# DemodTeensy.net
KiCad netlist of a schematic drawn in Altium Designer
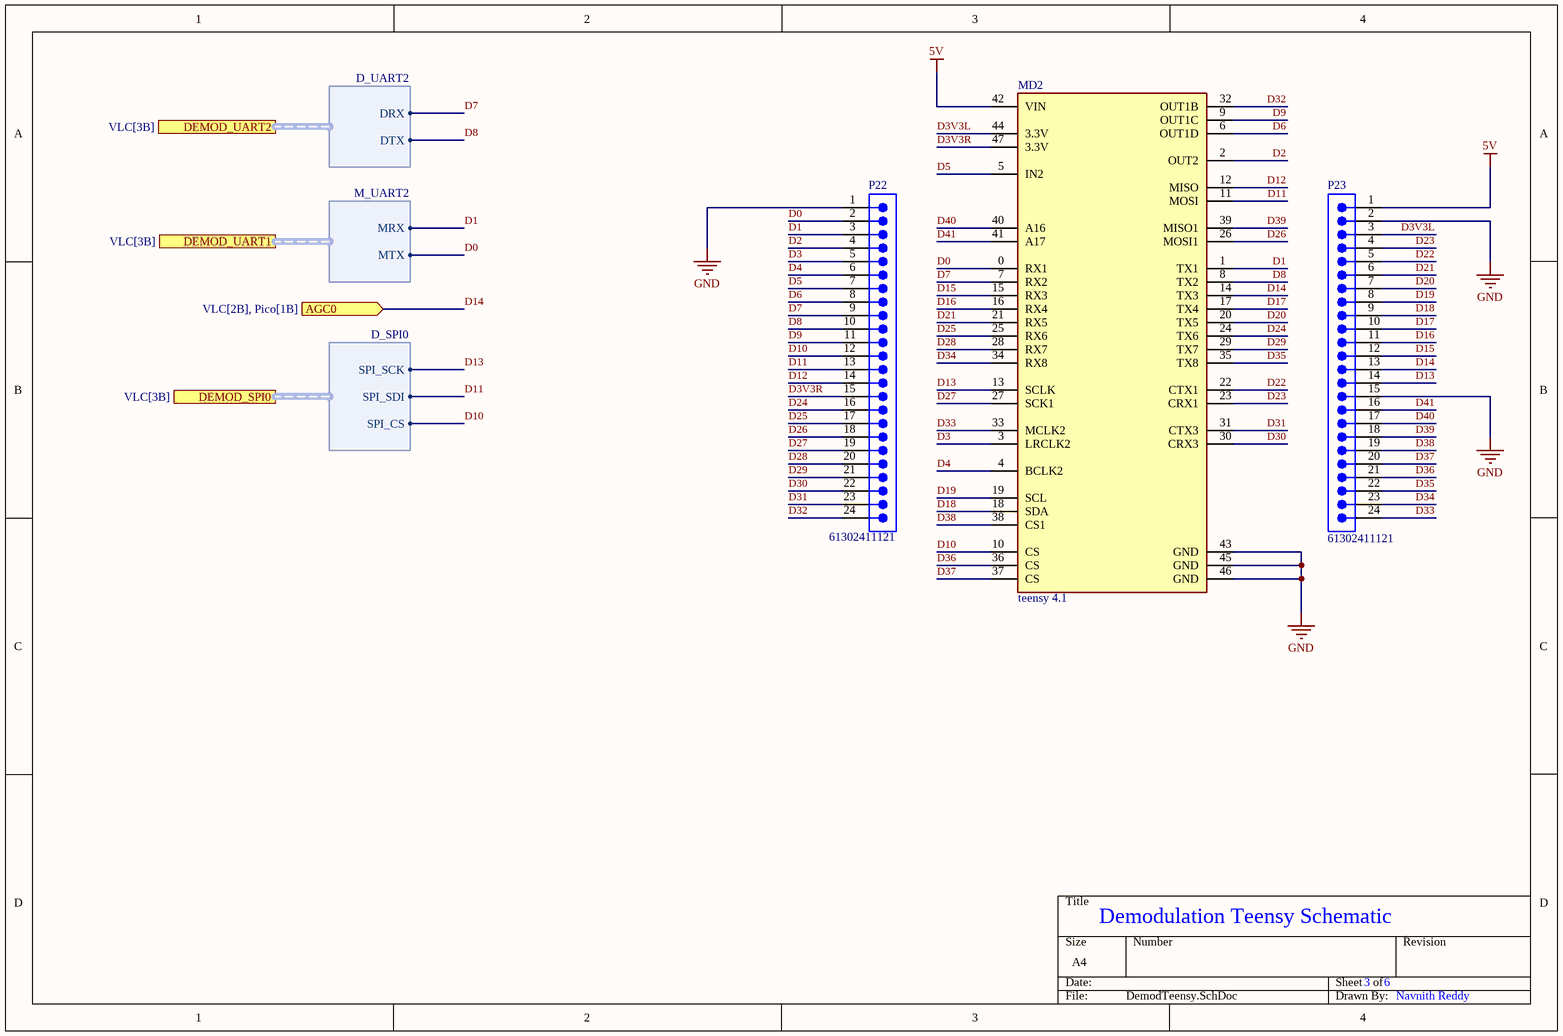
[diagram p0: DemodTeensy.SchDoc]

(export (version "E")
  (design (tool "Eeschema 10.0.6"))
  (components
    (comp (ref "MD2")
      (value "teensy 4.1")
      (footprint "FP-DEV-16996-MFG")
      (description "TEENSY 4.1 (HEADERS)")
      (libsource (lib "Altium Content Vault") (part "080115a1ce54750370cf87ec145ee29"))
    )
    (comp (ref "P22")
      (value "61302411121")
      (footprint "61302411121")
      (libsource (lib "Altium Content Vault") (part "Header_Male_1R_24P"))
    )
    (comp (ref "P23")
      (value "61302411121")
      (footprint "61302411121")
      (libsource (lib "Altium Content Vault") (part "Header_Male_1R_24P"))
    )
  )
  (nets
    (net (code "4") (name "/D0") (class "Default")
      (node (ref "MD2") (pin "0") (pinfunction "RX1_0") (pintype "passive"))
      (node (ref "P22") (pin "2") (pinfunction "2_2") (pintype "passive"))
    )
    (net (code "5") (name "/D1") (class "Default")
      (node (ref "MD2") (pin "1") (pinfunction "TX1_1") (pintype "passive"))
      (node (ref "P22") (pin "3") (pinfunction "3_3") (pintype "passive"))
    )
    (net (code "6") (name "/D2") (class "Default")
      (node (ref "MD2") (pin "2") (pinfunction "OUT2_2") (pintype "passive"))
      (node (ref "P22") (pin "4") (pinfunction "4_4") (pintype "passive"))
    )
    (net (code "7") (name "/D3") (class "Default")
      (node (ref "MD2") (pin "3") (pinfunction "LRCLK2_3") (pintype "passive"))
      (node (ref "P22") (pin "5") (pinfunction "5_5") (pintype "passive"))
    )
    (net (code "8") (name "/D3V3L") (class "Default")
      (node (ref "MD2") (pin "44") (pinfunction "3.3V_44") (pintype "passive"))
      (node (ref "P23") (pin "3") (pinfunction "3_3") (pintype "passive"))
    )
    (net (code "9") (name "/D3V3R") (class "Default")
      (node (ref "MD2") (pin "47") (pinfunction "3.3V_47") (pintype "passive"))
      (node (ref "P22") (pin "15") (pinfunction "15_15") (pintype "passive"))
    )
    (net (code "10") (name "/D4") (class "Default")
      (node (ref "MD2") (pin "4") (pinfunction "BCLK2_4") (pintype "passive"))
      (node (ref "P22") (pin "6") (pinfunction "6_6") (pintype "passive"))
    )
    (net (code "11") (name "/D5") (class "Default")
      (node (ref "MD2") (pin "5") (pinfunction "IN2_5") (pintype "passive"))
      (node (ref "P22") (pin "7") (pinfunction "7_7") (pintype "passive"))
    )
    (net (code "12") (name "/D6") (class "Default")
      (node (ref "MD2") (pin "6") (pinfunction "OUT1D_6") (pintype "passive"))
      (node (ref "P22") (pin "8") (pinfunction "8_8") (pintype "passive"))
    )
    (net (code "13") (name "/D7") (class "Default")
      (node (ref "MD2") (pin "7") (pinfunction "RX2_7") (pintype "passive"))
      (node (ref "P22") (pin "9") (pinfunction "9_9") (pintype "passive"))
    )
    (net (code "14") (name "/D8") (class "Default")
      (node (ref "MD2") (pin "8") (pinfunction "TX2_8") (pintype "passive"))
      (node (ref "P22") (pin "10") (pinfunction "10_10") (pintype "passive"))
    )
    (net (code "15") (name "/D9") (class "Default")
      (node (ref "MD2") (pin "9") (pinfunction "OUT1C_9") (pintype "passive"))
      (node (ref "P22") (pin "11") (pinfunction "11_11") (pintype "passive"))
    )
    (net (code "16") (name "/D10") (class "Default")
      (node (ref "MD2") (pin "10") (pinfunction "CS_10") (pintype "passive"))
      (node (ref "P22") (pin "12") (pinfunction "12_12") (pintype "passive"))
    )
    (net (code "17") (name "/D11") (class "Default")
      (node (ref "MD2") (pin "11") (pinfunction "MOSI_11") (pintype "passive"))
      (node (ref "P22") (pin "13") (pinfunction "13_13") (pintype "passive"))
    )
    (net (code "18") (name "/D12") (class "Default")
      (node (ref "MD2") (pin "12") (pinfunction "MISO_12") (pintype "passive"))
      (node (ref "P22") (pin "14") (pinfunction "14_14") (pintype "passive"))
    )
    (net (code "19") (name "/D13") (class "Default")
      (node (ref "MD2") (pin "13") (pinfunction "SCLK_13") (pintype "passive"))
      (node (ref "P23") (pin "14") (pinfunction "14_14") (pintype "passive"))
    )
    (net (code "20") (name "/D14") (class "Default")
      (node (ref "MD2") (pin "14") (pinfunction "TX3_14") (pintype "passive"))
      (node (ref "P23") (pin "13") (pinfunction "13_13") (pintype "passive"))
    )
    (net (code "21") (name "/D15") (class "Default")
      (node (ref "MD2") (pin "15") (pinfunction "RX3_15") (pintype "passive"))
      (node (ref "P23") (pin "12") (pinfunction "12_12") (pintype "passive"))
    )
    (net (code "22") (name "/D16") (class "Default")
      (node (ref "MD2") (pin "16") (pinfunction "RX4_16") (pintype "passive"))
      (node (ref "P23") (pin "11") (pinfunction "11_11") (pintype "passive"))
    )
    (net (code "23") (name "/D17") (class "Default")
      (node (ref "MD2") (pin "17") (pinfunction "TX4_17") (pintype "passive"))
      (node (ref "P23") (pin "10") (pinfunction "10_10") (pintype "passive"))
    )
    (net (code "24") (name "/D18") (class "Default")
      (node (ref "MD2") (pin "18") (pinfunction "SDA_18") (pintype "passive"))
      (node (ref "P23") (pin "9") (pinfunction "9_9") (pintype "passive"))
    )
    (net (code "25") (name "/D19") (class "Default")
      (node (ref "MD2") (pin "19") (pinfunction "SCL_19") (pintype "passive"))
      (node (ref "P23") (pin "8") (pinfunction "8_8") (pintype "passive"))
    )
    (net (code "26") (name "/D20") (class "Default")
      (node (ref "MD2") (pin "20") (pinfunction "TX5_20") (pintype "passive"))
      (node (ref "P23") (pin "7") (pinfunction "7_7") (pintype "passive"))
    )
    (net (code "27") (name "/D21") (class "Default")
      (node (ref "MD2") (pin "21") (pinfunction "RX5_21") (pintype "passive"))
      (node (ref "P23") (pin "6") (pinfunction "6_6") (pintype "passive"))
    )
    (net (code "28") (name "/D22") (class "Default")
      (node (ref "MD2") (pin "22") (pinfunction "CTX1_22") (pintype "passive"))
      (node (ref "P23") (pin "5") (pinfunction "5_5") (pintype "passive"))
    )
    (net (code "29") (name "/D23") (class "Default")
      (node (ref "MD2") (pin "23") (pinfunction "CRX1_23") (pintype "passive"))
      (node (ref "P23") (pin "4") (pinfunction "4_4") (pintype "passive"))
    )
    (net (code "30") (name "/D24") (class "Default")
      (node (ref "MD2") (pin "24") (pinfunction "TX6_24") (pintype "passive"))
      (node (ref "P22") (pin "16") (pinfunction "16_16") (pintype "passive"))
    )
    (net (code "31") (name "/D25") (class "Default")
      (node (ref "MD2") (pin "25") (pinfunction "RX6_25") (pintype "passive"))
      (node (ref "P22") (pin "17") (pinfunction "17_17") (pintype "passive"))
    )
    (net (code "32") (name "/D26") (class "Default")
      (node (ref "MD2") (pin "26") (pinfunction "MOSI1_26") (pintype "passive"))
      (node (ref "P22") (pin "18") (pinfunction "18_18") (pintype "passive"))
    )
    (net (code "33") (name "/D27") (class "Default")
      (node (ref "MD2") (pin "27") (pinfunction "SCK1_27") (pintype "passive"))
      (node (ref "P22") (pin "19") (pinfunction "19_19") (pintype "passive"))
    )
    (net (code "34") (name "/D28") (class "Default")
      (node (ref "MD2") (pin "28") (pinfunction "RX7_28") (pintype "passive"))
      (node (ref "P22") (pin "20") (pinfunction "20_20") (pintype "passive"))
    )
    (net (code "35") (name "/D29") (class "Default")
      (node (ref "MD2") (pin "29") (pinfunction "TX7_29") (pintype "passive"))
      (node (ref "P22") (pin "21") (pinfunction "21_21") (pintype "passive"))
    )
    (net (code "36") (name "/D30") (class "Default")
      (node (ref "MD2") (pin "30") (pinfunction "CRX3_30") (pintype "passive"))
      (node (ref "P22") (pin "22") (pinfunction "22_22") (pintype "passive"))
    )
    (net (code "37") (name "/D31") (class "Default")
      (node (ref "MD2") (pin "31") (pinfunction "CTX3_31") (pintype "passive"))
      (node (ref "P22") (pin "23") (pinfunction "23_23") (pintype "passive"))
    )
    (net (code "38") (name "/D32") (class "Default")
      (node (ref "MD2") (pin "32") (pinfunction "OUT1B_32") (pintype "passive"))
      (node (ref "P22") (pin "24") (pinfunction "24_24") (pintype "passive"))
    )
    (net (code "39") (name "/D33") (class "Default")
      (node (ref "MD2") (pin "33") (pinfunction "MCLK2_33") (pintype "passive"))
      (node (ref "P23") (pin "24") (pinfunction "24_24") (pintype "passive"))
    )
    (net (code "40") (name "/D34") (class "Default")
      (node (ref "MD2") (pin "34") (pinfunction "RX8_34") (pintype "passive"))
      (node (ref "P23") (pin "23") (pinfunction "23_23") (pintype "passive"))
    )
    (net (code "41") (name "/D35") (class "Default")
      (node (ref "MD2") (pin "35") (pinfunction "TX8_35") (pintype "passive"))
      (node (ref "P23") (pin "22") (pinfunction "22_22") (pintype "passive"))
    )
    (net (code "42") (name "/D36") (class "Default")
      (node (ref "MD2") (pin "36") (pinfunction "CS_36") (pintype "passive"))
      (node (ref "P23") (pin "21") (pinfunction "21_21") (pintype "passive"))
    )
    (net (code "43") (name "/D37") (class "Default")
      (node (ref "MD2") (pin "37") (pinfunction "CS_37") (pintype "passive"))
      (node (ref "P23") (pin "20") (pinfunction "20_20") (pintype "passive"))
    )
    (net (code "44") (name "/D38") (class "Default")
      (node (ref "MD2") (pin "38") (pinfunction "CS1_38") (pintype "passive"))
      (node (ref "P23") (pin "19") (pinfunction "19_19") (pintype "passive"))
    )
    (net (code "45") (name "/D39") (class "Default")
      (node (ref "MD2") (pin "39") (pinfunction "MISO1_39") (pintype "passive"))
      (node (ref "P23") (pin "18") (pinfunction "18_18") (pintype "passive"))
    )
    (net (code "46") (name "/D40") (class "Default")
      (node (ref "MD2") (pin "40") (pinfunction "A16_40") (pintype "passive"))
      (node (ref "P23") (pin "17") (pinfunction "17_17") (pintype "passive"))
    )
    (net (code "47") (name "/D41") (class "Default")
      (node (ref "MD2") (pin "41") (pinfunction "A17_41") (pintype "passive"))
      (node (ref "P23") (pin "16") (pinfunction "16_16") (pintype "passive"))
    )
    (net (code "51") (name "5V") (class "Default")
      (node (ref "MD2") (pin "42") (pinfunction "VIN_42") (pintype "passive"))
      (node (ref "P23") (pin "1") (pinfunction "1_1") (pintype "passive"))
    )
    (net (code "52") (name "GND") (class "Default")
      (node (ref "MD2") (pin "43") (pinfunction "GND_43") (pintype "passive"))
      (node (ref "MD2") (pin "45") (pinfunction "GND_45") (pintype "passive"))
      (node (ref "MD2") (pin "46") (pinfunction "GND_46") (pintype "passive"))
      (node (ref "P22") (pin "1") (pinfunction "1_1") (pintype "passive"))
      (node (ref "P23") (pin "15") (pinfunction "15_15") (pintype "passive"))
      (node (ref "P23") (pin "2") (pinfunction "2_2") (pintype "passive"))
    )
  )
)
